# bac-bmb-t.net
KiCad netlist of a schematic drawn in EAGLE
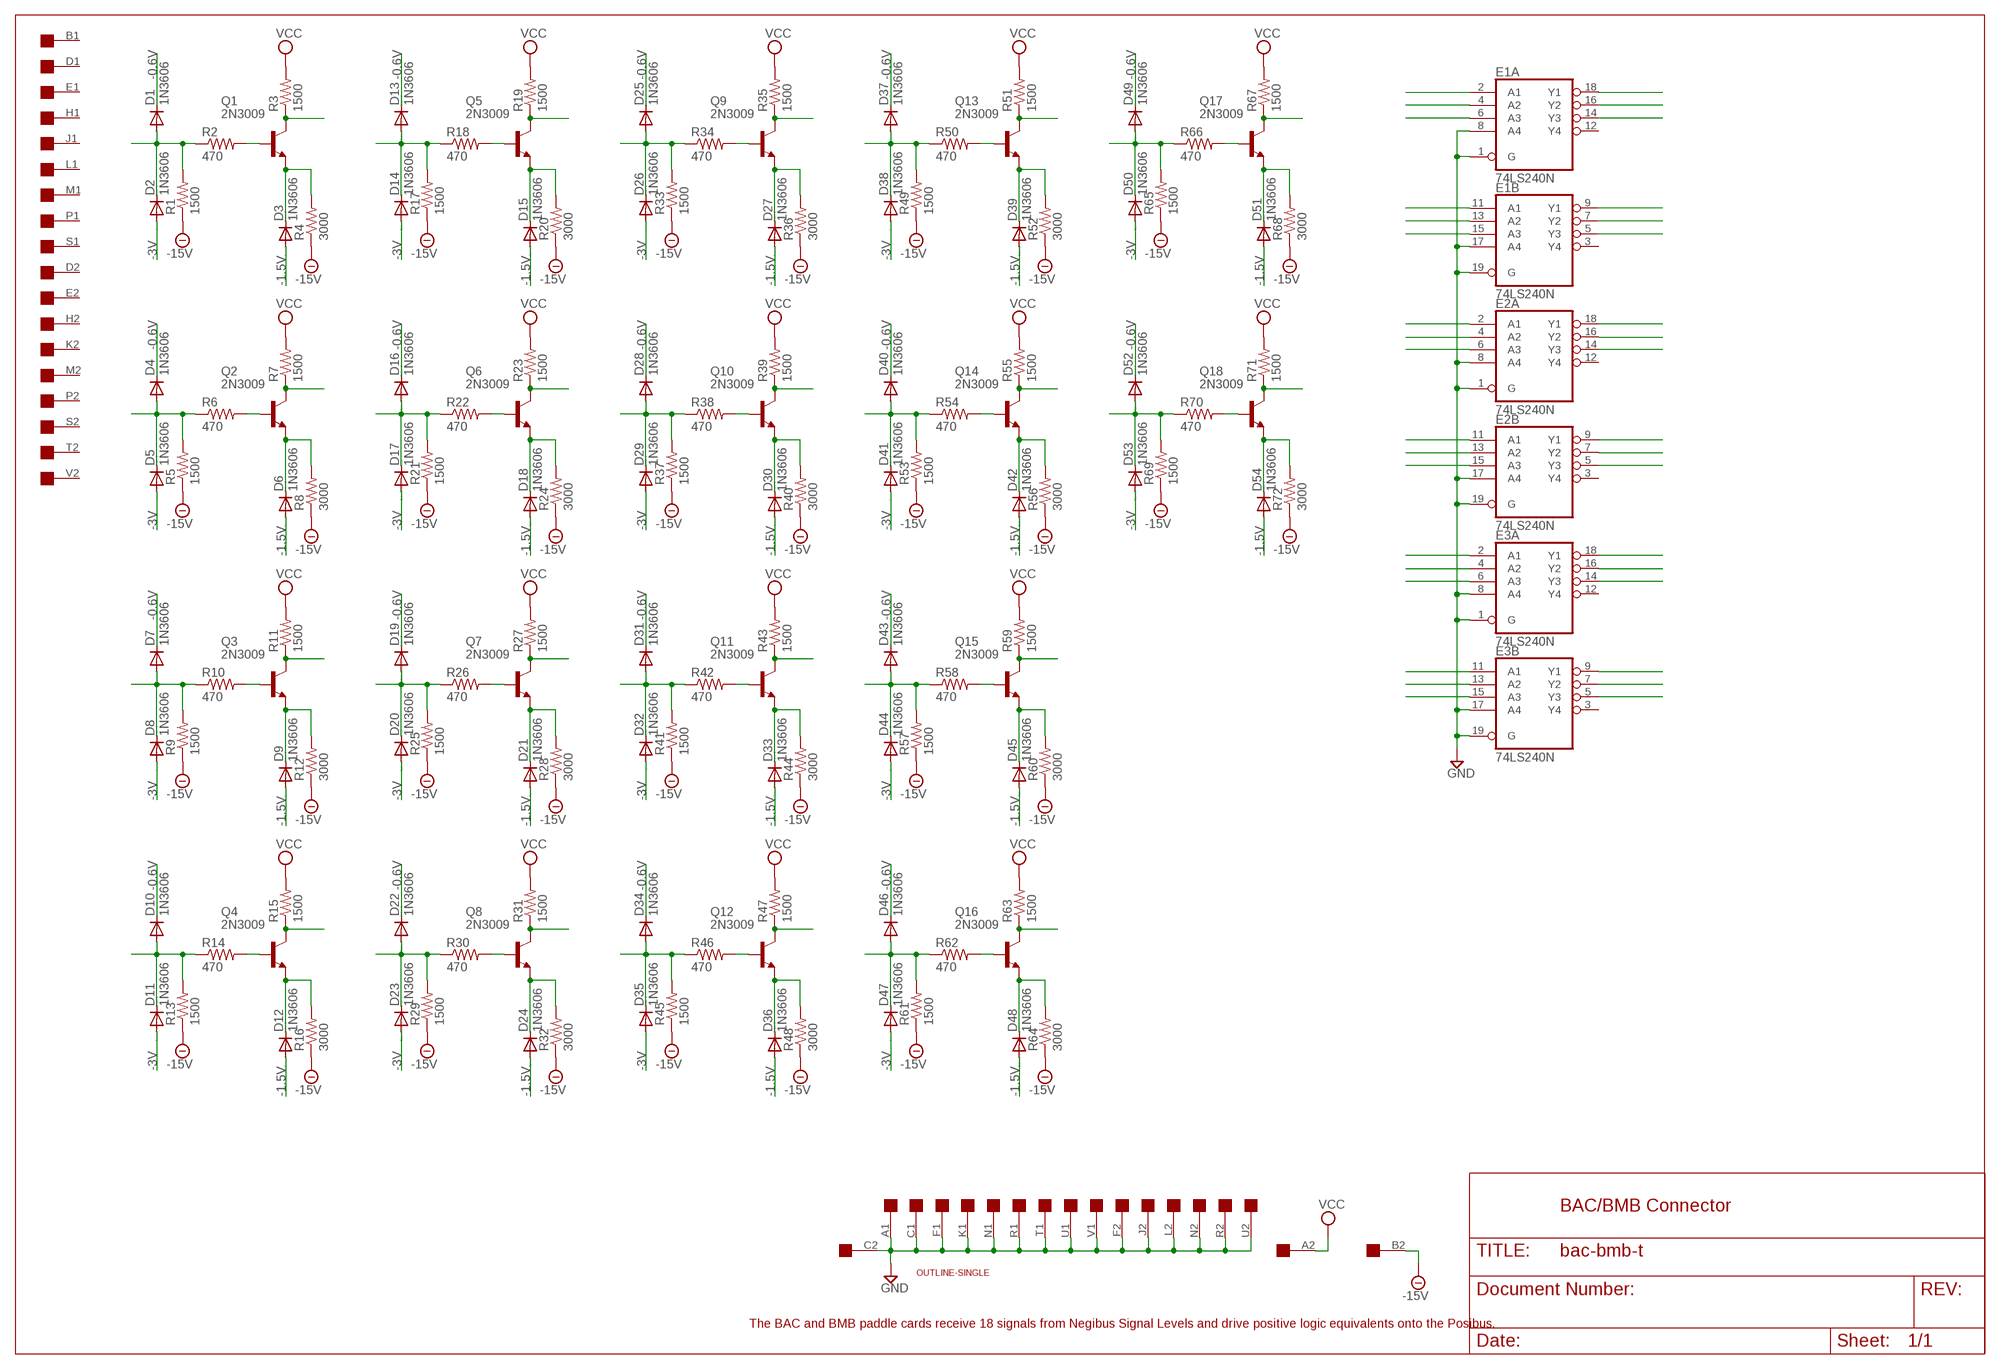
[diagram p0: schematic, sheet 1]

(export (version "E")
  (design (tool "Eeschema 10.0.6"))
  (components
    (comp (ref "D1")
      (value "1N3606")
      (footprint "eagle-import:DO35-10")
      (libsource (lib "eagle-import") (part "DIODE-DO35-10"))
    )
    (comp (ref "D2")
      (value "1N3606")
      (footprint "eagle-import:DO35-10")
      (libsource (lib "eagle-import") (part "DIODE-DO35-10"))
    )
    (comp (ref "D3")
      (value "1N3606")
      (footprint "eagle-import:DO35-10")
      (libsource (lib "eagle-import") (part "DIODE-DO35-10"))
    )
    (comp (ref "D4")
      (value "1N3606")
      (footprint "eagle-import:DO35-10")
      (libsource (lib "eagle-import") (part "DIODE-DO35-10"))
    )
    (comp (ref "D5")
      (value "1N3606")
      (footprint "eagle-import:DO35-10")
      (libsource (lib "eagle-import") (part "DIODE-DO35-10"))
    )
    (comp (ref "D6")
      (value "1N3606")
      (footprint "eagle-import:DO35-10")
      (libsource (lib "eagle-import") (part "DIODE-DO35-10"))
    )
    (comp (ref "D7")
      (value "1N3606")
      (footprint "eagle-import:DO35-10")
      (libsource (lib "eagle-import") (part "DIODE-DO35-10"))
    )
    (comp (ref "D8")
      (value "1N3606")
      (footprint "eagle-import:DO35-10")
      (libsource (lib "eagle-import") (part "DIODE-DO35-10"))
    )
    (comp (ref "D9")
      (value "1N3606")
      (footprint "eagle-import:DO35-10")
      (libsource (lib "eagle-import") (part "DIODE-DO35-10"))
    )
    (comp (ref "D10")
      (value "1N3606")
      (footprint "eagle-import:DO35-10")
      (libsource (lib "eagle-import") (part "DIODE-DO35-10"))
    )
    (comp (ref "D11")
      (value "1N3606")
      (footprint "eagle-import:DO35-10")
      (libsource (lib "eagle-import") (part "DIODE-DO35-10"))
    )
    (comp (ref "D12")
      (value "1N3606")
      (footprint "eagle-import:DO35-10")
      (libsource (lib "eagle-import") (part "DIODE-DO35-10"))
    )
    (comp (ref "D13")
      (value "1N3606")
      (footprint "eagle-import:DO35-10")
      (libsource (lib "eagle-import") (part "DIODE-DO35-10"))
    )
    (comp (ref "D14")
      (value "1N3606")
      (footprint "eagle-import:DO35-10")
      (libsource (lib "eagle-import") (part "DIODE-DO35-10"))
    )
    (comp (ref "D15")
      (value "1N3606")
      (footprint "eagle-import:DO35-10")
      (libsource (lib "eagle-import") (part "DIODE-DO35-10"))
    )
    (comp (ref "D16")
      (value "1N3606")
      (footprint "eagle-import:DO35-10")
      (libsource (lib "eagle-import") (part "DIODE-DO35-10"))
    )
    (comp (ref "D17")
      (value "1N3606")
      (footprint "eagle-import:DO35-10")
      (libsource (lib "eagle-import") (part "DIODE-DO35-10"))
    )
    (comp (ref "D18")
      (value "1N3606")
      (footprint "eagle-import:DO35-10")
      (libsource (lib "eagle-import") (part "DIODE-DO35-10"))
    )
    (comp (ref "D19")
      (value "1N3606")
      (footprint "eagle-import:DO35-10")
      (libsource (lib "eagle-import") (part "DIODE-DO35-10"))
    )
    (comp (ref "D20")
      (value "1N3606")
      (footprint "eagle-import:DO35-10")
      (libsource (lib "eagle-import") (part "DIODE-DO35-10"))
    )
    (comp (ref "D21")
      (value "1N3606")
      (footprint "eagle-import:DO35-10")
      (libsource (lib "eagle-import") (part "DIODE-DO35-10"))
    )
    (comp (ref "D22")
      (value "1N3606")
      (footprint "eagle-import:DO35-10")
      (libsource (lib "eagle-import") (part "DIODE-DO35-10"))
    )
    (comp (ref "D23")
      (value "1N3606")
      (footprint "eagle-import:DO35-10")
      (libsource (lib "eagle-import") (part "DIODE-DO35-10"))
    )
    (comp (ref "D24")
      (value "1N3606")
      (footprint "eagle-import:DO35-10")
      (libsource (lib "eagle-import") (part "DIODE-DO35-10"))
    )
    (comp (ref "D25")
      (value "1N3606")
      (footprint "eagle-import:DO35-10")
      (libsource (lib "eagle-import") (part "DIODE-DO35-10"))
    )
    (comp (ref "D26")
      (value "1N3606")
      (footprint "eagle-import:DO35-10")
      (libsource (lib "eagle-import") (part "DIODE-DO35-10"))
    )
    (comp (ref "D27")
      (value "1N3606")
      (footprint "eagle-import:DO35-10")
      (libsource (lib "eagle-import") (part "DIODE-DO35-10"))
    )
    (comp (ref "D28")
      (value "1N3606")
      (footprint "eagle-import:DO35-10")
      (libsource (lib "eagle-import") (part "DIODE-DO35-10"))
    )
    (comp (ref "D29")
      (value "1N3606")
      (footprint "eagle-import:DO35-10")
      (libsource (lib "eagle-import") (part "DIODE-DO35-10"))
    )
    (comp (ref "D30")
      (value "1N3606")
      (footprint "eagle-import:DO35-10")
      (libsource (lib "eagle-import") (part "DIODE-DO35-10"))
    )
    (comp (ref "D31")
      (value "1N3606")
      (footprint "eagle-import:DO35-10")
      (libsource (lib "eagle-import") (part "DIODE-DO35-10"))
    )
    (comp (ref "D32")
      (value "1N3606")
      (footprint "eagle-import:DO35-10")
      (libsource (lib "eagle-import") (part "DIODE-DO35-10"))
    )
    (comp (ref "D33")
      (value "1N3606")
      (footprint "eagle-import:DO35-10")
      (libsource (lib "eagle-import") (part "DIODE-DO35-10"))
    )
    (comp (ref "D34")
      (value "1N3606")
      (footprint "eagle-import:DO35-10")
      (libsource (lib "eagle-import") (part "DIODE-DO35-10"))
    )
    (comp (ref "D35")
      (value "1N3606")
      (footprint "eagle-import:DO35-10")
      (libsource (lib "eagle-import") (part "DIODE-DO35-10"))
    )
    (comp (ref "D36")
      (value "1N3606")
      (footprint "eagle-import:DO35-10")
      (libsource (lib "eagle-import") (part "DIODE-DO35-10"))
    )
    (comp (ref "D37")
      (value "1N3606")
      (footprint "eagle-import:DO35-10")
      (libsource (lib "eagle-import") (part "DIODE-DO35-10"))
    )
    (comp (ref "D38")
      (value "1N3606")
      (footprint "eagle-import:DO35-10")
      (libsource (lib "eagle-import") (part "DIODE-DO35-10"))
    )
    (comp (ref "D39")
      (value "1N3606")
      (footprint "eagle-import:DO35-10")
      (libsource (lib "eagle-import") (part "DIODE-DO35-10"))
    )
    (comp (ref "D40")
      (value "1N3606")
      (footprint "eagle-import:DO35-10")
      (libsource (lib "eagle-import") (part "DIODE-DO35-10"))
    )
    (comp (ref "D41")
      (value "1N3606")
      (footprint "eagle-import:DO35-10")
      (libsource (lib "eagle-import") (part "DIODE-DO35-10"))
    )
    (comp (ref "D42")
      (value "1N3606")
      (footprint "eagle-import:DO35-10")
      (libsource (lib "eagle-import") (part "DIODE-DO35-10"))
    )
    (comp (ref "D43")
      (value "1N3606")
      (footprint "eagle-import:DO35-10")
      (libsource (lib "eagle-import") (part "DIODE-DO35-10"))
    )
    (comp (ref "D44")
      (value "1N3606")
      (footprint "eagle-import:DO35-10")
      (libsource (lib "eagle-import") (part "DIODE-DO35-10"))
    )
    (comp (ref "D45")
      (value "1N3606")
      (footprint "eagle-import:DO35-10")
      (libsource (lib "eagle-import") (part "DIODE-DO35-10"))
    )
    (comp (ref "D46")
      (value "1N3606")
      (footprint "eagle-import:DO35-10")
      (libsource (lib "eagle-import") (part "DIODE-DO35-10"))
    )
    (comp (ref "D47")
      (value "1N3606")
      (footprint "eagle-import:DO35-10")
      (libsource (lib "eagle-import") (part "DIODE-DO35-10"))
    )
    (comp (ref "D48")
      (value "1N3606")
      (footprint "eagle-import:DO35-10")
      (libsource (lib "eagle-import") (part "DIODE-DO35-10"))
    )
    (comp (ref "D49")
      (value "1N3606")
      (footprint "eagle-import:DO35-10")
      (libsource (lib "eagle-import") (part "DIODE-DO35-10"))
    )
    (comp (ref "D50")
      (value "1N3606")
      (footprint "eagle-import:DO35-10")
      (libsource (lib "eagle-import") (part "DIODE-DO35-10"))
    )
    (comp (ref "D51")
      (value "1N3606")
      (footprint "eagle-import:DO35-10")
      (libsource (lib "eagle-import") (part "DIODE-DO35-10"))
    )
    (comp (ref "D52")
      (value "1N3606")
      (footprint "eagle-import:DO35-10")
      (libsource (lib "eagle-import") (part "DIODE-DO35-10"))
    )
    (comp (ref "D53")
      (value "1N3606")
      (footprint "eagle-import:DO35-10")
      (libsource (lib "eagle-import") (part "DIODE-DO35-10"))
    )
    (comp (ref "D54")
      (value "1N3606")
      (footprint "eagle-import:DO35-10")
      (libsource (lib "eagle-import") (part "DIODE-DO35-10"))
    )
    (comp (ref "E1")
      (value "74LS240N")
      (footprint "eagle-import:DIL20")
      (libsource (lib "eagle-import") (part "74240NLS"))
    )
    (comp (ref "E2")
      (value "74LS240N")
      (footprint "eagle-import:DIL20")
      (libsource (lib "eagle-import") (part "74240NLS"))
    )
    (comp (ref "E3")
      (value "74LS240N")
      (footprint "eagle-import:DIL20")
      (libsource (lib "eagle-import") (part "74240NLS"))
    )
    (comp (ref "Q1")
      (value "2N3009")
      (footprint "eagle-import:TO5")
      (libsource (lib "eagle-import") (part "-NPN-TO5"))
    )
    (comp (ref "Q2")
      (value "2N3009")
      (footprint "eagle-import:TO5")
      (libsource (lib "eagle-import") (part "-NPN-TO5"))
    )
    (comp (ref "Q3")
      (value "2N3009")
      (footprint "eagle-import:TO5")
      (libsource (lib "eagle-import") (part "-NPN-TO5"))
    )
    (comp (ref "Q4")
      (value "2N3009")
      (footprint "eagle-import:TO5")
      (libsource (lib "eagle-import") (part "-NPN-TO5"))
    )
    (comp (ref "Q5")
      (value "2N3009")
      (footprint "eagle-import:TO5")
      (libsource (lib "eagle-import") (part "-NPN-TO5"))
    )
    (comp (ref "Q6")
      (value "2N3009")
      (footprint "eagle-import:TO5")
      (libsource (lib "eagle-import") (part "-NPN-TO5"))
    )
    (comp (ref "Q7")
      (value "2N3009")
      (footprint "eagle-import:TO5")
      (libsource (lib "eagle-import") (part "-NPN-TO5"))
    )
    (comp (ref "Q8")
      (value "2N3009")
      (footprint "eagle-import:TO5")
      (libsource (lib "eagle-import") (part "-NPN-TO5"))
    )
    (comp (ref "Q9")
      (value "2N3009")
      (footprint "eagle-import:TO5")
      (libsource (lib "eagle-import") (part "-NPN-TO5"))
    )
    (comp (ref "Q10")
      (value "2N3009")
      (footprint "eagle-import:TO5")
      (libsource (lib "eagle-import") (part "-NPN-TO5"))
    )
    (comp (ref "Q11")
      (value "2N3009")
      (footprint "eagle-import:TO5")
      (libsource (lib "eagle-import") (part "-NPN-TO5"))
    )
    (comp (ref "Q12")
      (value "2N3009")
      (footprint "eagle-import:TO5")
      (libsource (lib "eagle-import") (part "-NPN-TO5"))
    )
    (comp (ref "Q13")
      (value "2N3009")
      (footprint "eagle-import:TO5")
      (libsource (lib "eagle-import") (part "-NPN-TO5"))
    )
    (comp (ref "Q14")
      (value "2N3009")
      (footprint "eagle-import:TO5")
      (libsource (lib "eagle-import") (part "-NPN-TO5"))
    )
    (comp (ref "Q15")
      (value "2N3009")
      (footprint "eagle-import:TO5")
      (libsource (lib "eagle-import") (part "-NPN-TO5"))
    )
    (comp (ref "Q16")
      (value "2N3009")
      (footprint "eagle-import:TO5")
      (libsource (lib "eagle-import") (part "-NPN-TO5"))
    )
    (comp (ref "Q17")
      (value "2N3009")
      (footprint "eagle-import:TO5")
      (libsource (lib "eagle-import") (part "-NPN-TO5"))
    )
    (comp (ref "Q18")
      (value "2N3009")
      (footprint "eagle-import:TO5")
      (libsource (lib "eagle-import") (part "-NPN-TO5"))
    )
    (comp (ref "R1")
      (value "1500")
      (footprint "eagle-import:0207_10")
      (libsource (lib "eagle-import") (part "R-US_0207/10"))
    )
    (comp (ref "R2")
      (value "470")
      (footprint "eagle-import:0207_10")
      (libsource (lib "eagle-import") (part "R-US_0207/10"))
    )
    (comp (ref "R3")
      (value "1500")
      (footprint "eagle-import:0207_10")
      (libsource (lib "eagle-import") (part "R-US_0207/10"))
    )
    (comp (ref "R4")
      (value "3000")
      (footprint "eagle-import:0207_10")
      (libsource (lib "eagle-import") (part "R-US_0207/10"))
    )
    (comp (ref "R5")
      (value "1500")
      (footprint "eagle-import:0207_10")
      (libsource (lib "eagle-import") (part "R-US_0207/10"))
    )
    (comp (ref "R6")
      (value "470")
      (footprint "eagle-import:0207_10")
      (libsource (lib "eagle-import") (part "R-US_0207/10"))
    )
    (comp (ref "R7")
      (value "1500")
      (footprint "eagle-import:0207_10")
      (libsource (lib "eagle-import") (part "R-US_0207/10"))
    )
    (comp (ref "R8")
      (value "3000")
      (footprint "eagle-import:0207_10")
      (libsource (lib "eagle-import") (part "R-US_0207/10"))
    )
    (comp (ref "R9")
      (value "1500")
      (footprint "eagle-import:0207_10")
      (libsource (lib "eagle-import") (part "R-US_0207/10"))
    )
    (comp (ref "R10")
      (value "470")
      (footprint "eagle-import:0207_10")
      (libsource (lib "eagle-import") (part "R-US_0207/10"))
    )
    (comp (ref "R11")
      (value "1500")
      (footprint "eagle-import:0207_10")
      (libsource (lib "eagle-import") (part "R-US_0207/10"))
    )
    (comp (ref "R12")
      (value "3000")
      (footprint "eagle-import:0207_10")
      (libsource (lib "eagle-import") (part "R-US_0207/10"))
    )
    (comp (ref "R13")
      (value "1500")
      (footprint "eagle-import:0207_10")
      (libsource (lib "eagle-import") (part "R-US_0207/10"))
    )
    (comp (ref "R14")
      (value "470")
      (footprint "eagle-import:0207_10")
      (libsource (lib "eagle-import") (part "R-US_0207/10"))
    )
    (comp (ref "R15")
      (value "1500")
      (footprint "eagle-import:0207_10")
      (libsource (lib "eagle-import") (part "R-US_0207/10"))
    )
    (comp (ref "R16")
      (value "3000")
      (footprint "eagle-import:0207_10")
      (libsource (lib "eagle-import") (part "R-US_0207/10"))
    )
    (comp (ref "R17")
      (value "1500")
      (footprint "eagle-import:0207_10")
      (libsource (lib "eagle-import") (part "R-US_0207/10"))
    )
    (comp (ref "R18")
      (value "470")
      (footprint "eagle-import:0207_10")
      (libsource (lib "eagle-import") (part "R-US_0207/10"))
    )
    (comp (ref "R19")
      (value "1500")
      (footprint "eagle-import:0207_10")
      (libsource (lib "eagle-import") (part "R-US_0207/10"))
    )
    (comp (ref "R20")
      (value "3000")
      (footprint "eagle-import:0207_10")
      (libsource (lib "eagle-import") (part "R-US_0207/10"))
    )
    (comp (ref "R21")
      (value "1500")
      (footprint "eagle-import:0207_10")
      (libsource (lib "eagle-import") (part "R-US_0207/10"))
    )
    (comp (ref "R22")
      (value "470")
      (footprint "eagle-import:0207_10")
      (libsource (lib "eagle-import") (part "R-US_0207/10"))
    )
    (comp (ref "R23")
      (value "1500")
      (footprint "eagle-import:0207_10")
      (libsource (lib "eagle-import") (part "R-US_0207/10"))
    )
    (comp (ref "R24")
      (value "3000")
      (footprint "eagle-import:0207_10")
      (libsource (lib "eagle-import") (part "R-US_0207/10"))
    )
    (comp (ref "R25")
      (value "1500")
      (footprint "eagle-import:0207_10")
      (libsource (lib "eagle-import") (part "R-US_0207/10"))
    )
    (comp (ref "R26")
      (value "470")
      (footprint "eagle-import:0207_10")
      (libsource (lib "eagle-import") (part "R-US_0207/10"))
    )
    (comp (ref "R27")
      (value "1500")
      (footprint "eagle-import:0207_10")
      (libsource (lib "eagle-import") (part "R-US_0207/10"))
    )
    (comp (ref "R28")
      (value "3000")
      (footprint "eagle-import:0207_10")
      (libsource (lib "eagle-import") (part "R-US_0207/10"))
    )
    (comp (ref "R29")
      (value "1500")
      (footprint "eagle-import:0207_10")
      (libsource (lib "eagle-import") (part "R-US_0207/10"))
    )
    (comp (ref "R30")
      (value "470")
      (footprint "eagle-import:0207_10")
      (libsource (lib "eagle-import") (part "R-US_0207/10"))
    )
    (comp (ref "R31")
      (value "1500")
      (footprint "eagle-import:0207_10")
      (libsource (lib "eagle-import") (part "R-US_0207/10"))
    )
    (comp (ref "R32")
      (value "3000")
      (footprint "eagle-import:0207_10")
      (libsource (lib "eagle-import") (part "R-US_0207/10"))
    )
    (comp (ref "R33")
      (value "1500")
      (footprint "eagle-import:0207_10")
      (libsource (lib "eagle-import") (part "R-US_0207/10"))
    )
    (comp (ref "R34")
      (value "470")
      (footprint "eagle-import:0207_10")
      (libsource (lib "eagle-import") (part "R-US_0207/10"))
    )
    (comp (ref "R35")
      (value "1500")
      (footprint "eagle-import:0207_10")
      (libsource (lib "eagle-import") (part "R-US_0207/10"))
    )
    (comp (ref "R36")
      (value "3000")
      (footprint "eagle-import:0207_10")
      (libsource (lib "eagle-import") (part "R-US_0207/10"))
    )
    (comp (ref "R37")
      (value "1500")
      (footprint "eagle-import:0207_10")
      (libsource (lib "eagle-import") (part "R-US_0207/10"))
    )
    (comp (ref "R38")
      (value "470")
      (footprint "eagle-import:0207_10")
      (libsource (lib "eagle-import") (part "R-US_0207/10"))
    )
    (comp (ref "R39")
      (value "1500")
      (footprint "eagle-import:0207_10")
      (libsource (lib "eagle-import") (part "R-US_0207/10"))
    )
    (comp (ref "R40")
      (value "3000")
      (footprint "eagle-import:0207_10")
      (libsource (lib "eagle-import") (part "R-US_0207/10"))
    )
    (comp (ref "R41")
      (value "1500")
      (footprint "eagle-import:0207_10")
      (libsource (lib "eagle-import") (part "R-US_0207/10"))
    )
    (comp (ref "R42")
      (value "470")
      (footprint "eagle-import:0207_10")
      (libsource (lib "eagle-import") (part "R-US_0207/10"))
    )
    (comp (ref "R43")
      (value "1500")
      (footprint "eagle-import:0207_10")
      (libsource (lib "eagle-import") (part "R-US_0207/10"))
    )
    (comp (ref "R44")
      (value "3000")
      (footprint "eagle-import:0207_10")
      (libsource (lib "eagle-import") (part "R-US_0207/10"))
    )
    (comp (ref "R45")
      (value "1500")
      (footprint "eagle-import:0207_10")
      (libsource (lib "eagle-import") (part "R-US_0207/10"))
    )
    (comp (ref "R46")
      (value "470")
      (footprint "eagle-import:0207_10")
      (libsource (lib "eagle-import") (part "R-US_0207/10"))
    )
    (comp (ref "R47")
      (value "1500")
      (footprint "eagle-import:0207_10")
      (libsource (lib "eagle-import") (part "R-US_0207/10"))
    )
    (comp (ref "R48")
      (value "3000")
      (footprint "eagle-import:0207_10")
      (libsource (lib "eagle-import") (part "R-US_0207/10"))
    )
    (comp (ref "R49")
      (value "1500")
      (footprint "eagle-import:0207_10")
      (libsource (lib "eagle-import") (part "R-US_0207/10"))
    )
    (comp (ref "R50")
      (value "470")
      (footprint "eagle-import:0207_10")
      (libsource (lib "eagle-import") (part "R-US_0207/10"))
    )
    (comp (ref "R51")
      (value "1500")
      (footprint "eagle-import:0207_10")
      (libsource (lib "eagle-import") (part "R-US_0207/10"))
    )
    (comp (ref "R52")
      (value "3000")
      (footprint "eagle-import:0207_10")
      (libsource (lib "eagle-import") (part "R-US_0207/10"))
    )
    (comp (ref "R53")
      (value "1500")
      (footprint "eagle-import:0207_10")
      (libsource (lib "eagle-import") (part "R-US_0207/10"))
    )
    (comp (ref "R54")
      (value "470")
      (footprint "eagle-import:0207_10")
      (libsource (lib "eagle-import") (part "R-US_0207/10"))
    )
    (comp (ref "R55")
      (value "1500")
      (footprint "eagle-import:0207_10")
      (libsource (lib "eagle-import") (part "R-US_0207/10"))
    )
    (comp (ref "R56")
      (value "3000")
      (footprint "eagle-import:0207_10")
      (libsource (lib "eagle-import") (part "R-US_0207/10"))
    )
    (comp (ref "R57")
      (value "1500")
      (footprint "eagle-import:0207_10")
      (libsource (lib "eagle-import") (part "R-US_0207/10"))
    )
    (comp (ref "R58")
      (value "470")
      (footprint "eagle-import:0207_10")
      (libsource (lib "eagle-import") (part "R-US_0207/10"))
    )
    (comp (ref "R59")
      (value "1500")
      (footprint "eagle-import:0207_10")
      (libsource (lib "eagle-import") (part "R-US_0207/10"))
    )
    (comp (ref "R60")
      (value "3000")
      (footprint "eagle-import:0207_10")
      (libsource (lib "eagle-import") (part "R-US_0207/10"))
    )
    (comp (ref "R61")
      (value "1500")
      (footprint "eagle-import:0207_10")
      (libsource (lib "eagle-import") (part "R-US_0207/10"))
    )
    (comp (ref "R62")
      (value "470")
      (footprint "eagle-import:0207_10")
      (libsource (lib "eagle-import") (part "R-US_0207/10"))
    )
    (comp (ref "R63")
      (value "1500")
      (footprint "eagle-import:0207_10")
      (libsource (lib "eagle-import") (part "R-US_0207/10"))
    )
    (comp (ref "R64")
      (value "3000")
      (footprint "eagle-import:0207_10")
      (libsource (lib "eagle-import") (part "R-US_0207/10"))
    )
    (comp (ref "R65")
      (value "1500")
      (footprint "eagle-import:0207_10")
      (libsource (lib "eagle-import") (part "R-US_0207/10"))
    )
    (comp (ref "R66")
      (value "470")
      (footprint "eagle-import:0207_10")
      (libsource (lib "eagle-import") (part "R-US_0207/10"))
    )
    (comp (ref "R67")
      (value "1500")
      (footprint "eagle-import:0207_10")
      (libsource (lib "eagle-import") (part "R-US_0207/10"))
    )
    (comp (ref "R68")
      (value "3000")
      (footprint "eagle-import:0207_10")
      (libsource (lib "eagle-import") (part "R-US_0207/10"))
    )
    (comp (ref "R69")
      (value "1500")
      (footprint "eagle-import:0207_10")
      (libsource (lib "eagle-import") (part "R-US_0207/10"))
    )
    (comp (ref "R70")
      (value "470")
      (footprint "eagle-import:0207_10")
      (libsource (lib "eagle-import") (part "R-US_0207/10"))
    )
    (comp (ref "R71")
      (value "1500")
      (footprint "eagle-import:0207_10")
      (libsource (lib "eagle-import") (part "R-US_0207/10"))
    )
    (comp (ref "R72")
      (value "3000")
      (footprint "eagle-import:0207_10")
      (libsource (lib "eagle-import") (part "R-US_0207/10"))
    )
    (comp (ref "U$1")
      (value "SINGLE")
      (footprint "eagle-import:EDGE-CON2")
      (libsource (lib "eagle-import") (part "SINGLE"))
    )
    (comp (ref "U$2")
      (value "OUTLINE-SINGLE")
      (footprint "eagle-import:SINGLE")
      (libsource (lib "eagle-import") (part "OUTLINE-SINGLE"))
    )
  )
  (nets
    (net (code "1") (name "-15V") (class "Default")
      (node (ref "R1") (pin "1") (pinfunction "1_1") (pintype "passive"))
      (node (ref "R12") (pin "1") (pinfunction "1_1") (pintype "passive"))
      (node (ref "R13") (pin "1") (pinfunction "1_1") (pintype "passive"))
      (node (ref "R16") (pin "1") (pinfunction "1_1") (pintype "passive"))
      (node (ref "R17") (pin "1") (pinfunction "1_1") (pintype "passive"))
      (node (ref "R20") (pin "1") (pinfunction "1_1") (pintype "passive"))
      (node (ref "R21") (pin "1") (pinfunction "1_1") (pintype "passive"))
      (node (ref "R24") (pin "1") (pinfunction "1_1") (pintype "passive"))
      (node (ref "R25") (pin "1") (pinfunction "1_1") (pintype "passive"))
      (node (ref "R28") (pin "1") (pinfunction "1_1") (pintype "passive"))
      (node (ref "R29") (pin "1") (pinfunction "1_1") (pintype "passive"))
      (node (ref "R32") (pin "1") (pinfunction "1_1") (pintype "passive"))
      (node (ref "R33") (pin "1") (pinfunction "1_1") (pintype "passive"))
      (node (ref "R36") (pin "1") (pinfunction "1_1") (pintype "passive"))
      (node (ref "R37") (pin "1") (pinfunction "1_1") (pintype "passive"))
      (node (ref "R4") (pin "1") (pinfunction "1_1") (pintype "passive"))
      (node (ref "R40") (pin "1") (pinfunction "1_1") (pintype "passive"))
      (node (ref "R41") (pin "1") (pinfunction "1_1") (pintype "passive"))
      (node (ref "R44") (pin "1") (pinfunction "1_1") (pintype "passive"))
      (node (ref "R45") (pin "1") (pinfunction "1_1") (pintype "passive"))
      (node (ref "R48") (pin "1") (pinfunction "1_1") (pintype "passive"))
      (node (ref "R49") (pin "1") (pinfunction "1_1") (pintype "passive"))
      (node (ref "R5") (pin "1") (pinfunction "1_1") (pintype "passive"))
      (node (ref "R52") (pin "1") (pinfunction "1_1") (pintype "passive"))
      (node (ref "R53") (pin "1") (pinfunction "1_1") (pintype "passive"))
      (node (ref "R56") (pin "1") (pinfunction "1_1") (pintype "passive"))
      (node (ref "R57") (pin "1") (pinfunction "1_1") (pintype "passive"))
      (node (ref "R60") (pin "1") (pinfunction "1_1") (pintype "passive"))
      (node (ref "R61") (pin "1") (pinfunction "1_1") (pintype "passive"))
      (node (ref "R64") (pin "1") (pinfunction "1_1") (pintype "passive"))
      (node (ref "R65") (pin "1") (pinfunction "1_1") (pintype "passive"))
      (node (ref "R68") (pin "1") (pinfunction "1_1") (pintype "passive"))
      (node (ref "R69") (pin "1") (pinfunction "1_1") (pintype "passive"))
      (node (ref "R72") (pin "1") (pinfunction "1_1") (pintype "passive"))
      (node (ref "R8") (pin "1") (pinfunction "1_1") (pintype "passive"))
      (node (ref "R9") (pin "1") (pinfunction "1_1") (pintype "passive"))
      (node (ref "U$1") (pin "B2") (pinfunction "1_B2") (pintype "bidirectional"))
    )
    (net (code "2") (name "/-0.6V") (class "Default")
      (node (ref "D1") (pin "C") (pinfunction "C_C") (pintype "passive"))
      (node (ref "D10") (pin "C") (pinfunction "C_C") (pintype "passive"))
      (node (ref "D13") (pin "C") (pinfunction "C_C") (pintype "passive"))
      (node (ref "D16") (pin "C") (pinfunction "C_C") (pintype "passive"))
      (node (ref "D19") (pin "C") (pinfunction "C_C") (pintype "passive"))
      (node (ref "D22") (pin "C") (pinfunction "C_C") (pintype "passive"))
      (node (ref "D25") (pin "C") (pinfunction "C_C") (pintype "passive"))
      (node (ref "D28") (pin "C") (pinfunction "C_C") (pintype "passive"))
      (node (ref "D31") (pin "C") (pinfunction "C_C") (pintype "passive"))
      (node (ref "D34") (pin "C") (pinfunction "C_C") (pintype "passive"))
      (node (ref "D37") (pin "C") (pinfunction "C_C") (pintype "passive"))
      (node (ref "D4") (pin "C") (pinfunction "C_C") (pintype "passive"))
      (node (ref "D40") (pin "C") (pinfunction "C_C") (pintype "passive"))
      (node (ref "D43") (pin "C") (pinfunction "C_C") (pintype "passive"))
      (node (ref "D46") (pin "C") (pinfunction "C_C") (pintype "passive"))
      (node (ref "D49") (pin "C") (pinfunction "C_C") (pintype "passive"))
      (node (ref "D52") (pin "C") (pinfunction "C_C") (pintype "passive"))
      (node (ref "D7") (pin "C") (pinfunction "C_C") (pintype "passive"))
    )
    (net (code "3") (name "/-1.5V") (class "Default")
      (node (ref "D12") (pin "A") (pinfunction "A_A") (pintype "passive"))
      (node (ref "D15") (pin "A") (pinfunction "A_A") (pintype "passive"))
      (node (ref "D18") (pin "A") (pinfunction "A_A") (pintype "passive"))
      (node (ref "D21") (pin "A") (pinfunction "A_A") (pintype "passive"))
      (node (ref "D24") (pin "A") (pinfunction "A_A") (pintype "passive"))
      (node (ref "D27") (pin "A") (pinfunction "A_A") (pintype "passive"))
      (node (ref "D3") (pin "A") (pinfunction "A_A") (pintype "passive"))
      (node (ref "D30") (pin "A") (pinfunction "A_A") (pintype "passive"))
      (node (ref "D33") (pin "A") (pinfunction "A_A") (pintype "passive"))
      (node (ref "D36") (pin "A") (pinfunction "A_A") (pintype "passive"))
      (node (ref "D39") (pin "A") (pinfunction "A_A") (pintype "passive"))
      (node (ref "D42") (pin "A") (pinfunction "A_A") (pintype "passive"))
      (node (ref "D45") (pin "A") (pinfunction "A_A") (pintype "passive"))
      (node (ref "D48") (pin "A") (pinfunction "A_A") (pintype "passive"))
      (node (ref "D51") (pin "A") (pinfunction "A_A") (pintype "passive"))
      (node (ref "D54") (pin "A") (pinfunction "A_A") (pintype "passive"))
      (node (ref "D6") (pin "A") (pinfunction "A_A") (pintype "passive"))
      (node (ref "D9") (pin "A") (pinfunction "A_A") (pintype "passive"))
    )
    (net (code "4") (name "/-3V") (class "Default")
      (node (ref "D11") (pin "A") (pinfunction "A_A") (pintype "passive"))
      (node (ref "D14") (pin "A") (pinfunction "A_A") (pintype "passive"))
      (node (ref "D17") (pin "A") (pinfunction "A_A") (pintype "passive"))
      (node (ref "D2") (pin "A") (pinfunction "A_A") (pintype "passive"))
      (node (ref "D20") (pin "A") (pinfunction "A_A") (pintype "passive"))
      (node (ref "D23") (pin "A") (pinfunction "A_A") (pintype "passive"))
      (node (ref "D26") (pin "A") (pinfunction "A_A") (pintype "passive"))
      (node (ref "D29") (pin "A") (pinfunction "A_A") (pintype "passive"))
      (node (ref "D32") (pin "A") (pinfunction "A_A") (pintype "passive"))
      (node (ref "D35") (pin "A") (pinfunction "A_A") (pintype "passive"))
      (node (ref "D38") (pin "A") (pinfunction "A_A") (pintype "passive"))
      (node (ref "D41") (pin "A") (pinfunction "A_A") (pintype "passive"))
      (node (ref "D44") (pin "A") (pinfunction "A_A") (pintype "passive"))
      (node (ref "D47") (pin "A") (pinfunction "A_A") (pintype "passive"))
      (node (ref "D5") (pin "A") (pinfunction "A_A") (pintype "passive"))
      (node (ref "D50") (pin "A") (pinfunction "A_A") (pintype "passive"))
      (node (ref "D53") (pin "A") (pinfunction "A_A") (pintype "passive"))
      (node (ref "D8") (pin "A") (pinfunction "A_A") (pintype "passive"))
    )
    (net (code "5") (name "GND") (class "Default")
      (node (ref "E1") (pin "1") (pinfunction "G_1") (pintype "input"))
      (node (ref "E1") (pin "17") (pinfunction "A4_17") (pintype "input"))
      (node (ref "E1") (pin "19") (pinfunction "G_19") (pintype "input"))
      (node (ref "E1") (pin "8") (pinfunction "A4_8") (pintype "input"))
      (node (ref "E2") (pin "1") (pinfunction "G_1") (pintype "input"))
      (node (ref "E2") (pin "17") (pinfunction "A4_17") (pintype "input"))
      (node (ref "E2") (pin "19") (pinfunction "G_19") (pintype "input"))
      (node (ref "E2") (pin "8") (pinfunction "A4_8") (pintype "input"))
      (node (ref "E3") (pin "1") (pinfunction "G_1") (pintype "input"))
      (node (ref "E3") (pin "17") (pinfunction "A4_17") (pintype "input"))
      (node (ref "E3") (pin "19") (pinfunction "G_19") (pintype "input"))
      (node (ref "E3") (pin "8") (pinfunction "A4_8") (pintype "input"))
      (node (ref "U$1") (pin "A1") (pinfunction "1_A1") (pintype "bidirectional"))
      (node (ref "U$1") (pin "C1") (pinfunction "1_C1") (pintype "bidirectional"))
      (node (ref "U$1") (pin "C2") (pinfunction "1_C2") (pintype "bidirectional"))
      (node (ref "U$1") (pin "F1") (pinfunction "1_F1") (pintype "bidirectional"))
      (node (ref "U$1") (pin "F2") (pinfunction "1_F2") (pintype "bidirectional"))
      (node (ref "U$1") (pin "J2") (pinfunction "1_J2") (pintype "bidirectional"))
      (node (ref "U$1") (pin "K1") (pinfunction "1_K1") (pintype "bidirectional"))
      (node (ref "U$1") (pin "L2") (pinfunction "1_L2") (pintype "bidirectional"))
      (node (ref "U$1") (pin "N1") (pinfunction "1_N1") (pintype "bidirectional"))
      (node (ref "U$1") (pin "N2") (pinfunction "1_N2") (pintype "bidirectional"))
      (node (ref "U$1") (pin "R1") (pinfunction "1_R1") (pintype "bidirectional"))
      (node (ref "U$1") (pin "R2") (pinfunction "1_R2") (pintype "bidirectional"))
      (node (ref "U$1") (pin "T1") (pinfunction "1_T1") (pintype "bidirectional"))
      (node (ref "U$1") (pin "U1") (pinfunction "1_U1") (pintype "bidirectional"))
      (node (ref "U$1") (pin "U2") (pinfunction "1_U2") (pintype "bidirectional"))
      (node (ref "U$1") (pin "V1") (pinfunction "1_V1") (pintype "bidirectional"))
    )
    (net (code "6") (name "Net-(D1-PadA)") (class "Default")
      (node (ref "D1") (pin "A") (pinfunction "A_A") (pintype "passive"))
      (node (ref "D2") (pin "C") (pinfunction "C_C") (pintype "passive"))
      (node (ref "R1") (pin "2") (pinfunction "2_2") (pintype "passive"))
      (node (ref "R2") (pin "1") (pinfunction "1_1") (pintype "passive"))
    )
    (net (code "7") (name "Net-(D4-PadA)") (class "Default")
      (node (ref "D4") (pin "A") (pinfunction "A_A") (pintype "passive"))
      (node (ref "D5") (pin "C") (pinfunction "C_C") (pintype "passive"))
      (node (ref "R5") (pin "2") (pinfunction "2_2") (pintype "passive"))
      (node (ref "R6") (pin "1") (pinfunction "1_1") (pintype "passive"))
    )
    (net (code "8") (name "Net-(D7-PadA)") (class "Default")
      (node (ref "D7") (pin "A") (pinfunction "A_A") (pintype "passive"))
      (node (ref "D8") (pin "C") (pinfunction "C_C") (pintype "passive"))
      (node (ref "R10") (pin "1") (pinfunction "1_1") (pintype "passive"))
      (node (ref "R9") (pin "2") (pinfunction "2_2") (pintype "passive"))
    )
    (net (code "9") (name "Net-(D10-PadA)") (class "Default")
      (node (ref "D10") (pin "A") (pinfunction "A_A") (pintype "passive"))
      (node (ref "D11") (pin "C") (pinfunction "C_C") (pintype "passive"))
      (node (ref "R13") (pin "2") (pinfunction "2_2") (pintype "passive"))
      (node (ref "R14") (pin "1") (pinfunction "1_1") (pintype "passive"))
    )
    (net (code "10") (name "Net-(D13-PadA)") (class "Default")
      (node (ref "D13") (pin "A") (pinfunction "A_A") (pintype "passive"))
      (node (ref "D14") (pin "C") (pinfunction "C_C") (pintype "passive"))
      (node (ref "R17") (pin "2") (pinfunction "2_2") (pintype "passive"))
      (node (ref "R18") (pin "1") (pinfunction "1_1") (pintype "passive"))
    )
    (net (code "11") (name "Net-(D16-PadA)") (class "Default")
      (node (ref "D16") (pin "A") (pinfunction "A_A") (pintype "passive"))
      (node (ref "D17") (pin "C") (pinfunction "C_C") (pintype "passive"))
      (node (ref "R21") (pin "2") (pinfunction "2_2") (pintype "passive"))
      (node (ref "R22") (pin "1") (pinfunction "1_1") (pintype "passive"))
    )
    (net (code "12") (name "Net-(D19-PadA)") (class "Default")
      (node (ref "D19") (pin "A") (pinfunction "A_A") (pintype "passive"))
      (node (ref "D20") (pin "C") (pinfunction "C_C") (pintype "passive"))
      (node (ref "R25") (pin "2") (pinfunction "2_2") (pintype "passive"))
      (node (ref "R26") (pin "1") (pinfunction "1_1") (pintype "passive"))
    )
    (net (code "13") (name "Net-(D22-PadA)") (class "Default")
      (node (ref "D22") (pin "A") (pinfunction "A_A") (pintype "passive"))
      (node (ref "D23") (pin "C") (pinfunction "C_C") (pintype "passive"))
      (node (ref "R29") (pin "2") (pinfunction "2_2") (pintype "passive"))
      (node (ref "R30") (pin "1") (pinfunction "1_1") (pintype "passive"))
    )
    (net (code "14") (name "Net-(D25-PadA)") (class "Default")
      (node (ref "D25") (pin "A") (pinfunction "A_A") (pintype "passive"))
      (node (ref "D26") (pin "C") (pinfunction "C_C") (pintype "passive"))
      (node (ref "R33") (pin "2") (pinfunction "2_2") (pintype "passive"))
      (node (ref "R34") (pin "1") (pinfunction "1_1") (pintype "passive"))
    )
    (net (code "15") (name "Net-(D28-PadA)") (class "Default")
      (node (ref "D28") (pin "A") (pinfunction "A_A") (pintype "passive"))
      (node (ref "D29") (pin "C") (pinfunction "C_C") (pintype "passive"))
      (node (ref "R37") (pin "2") (pinfunction "2_2") (pintype "passive"))
      (node (ref "R38") (pin "1") (pinfunction "1_1") (pintype "passive"))
    )
    (net (code "16") (name "Net-(D31-PadA)") (class "Default")
      (node (ref "D31") (pin "A") (pinfunction "A_A") (pintype "passive"))
      (node (ref "D32") (pin "C") (pinfunction "C_C") (pintype "passive"))
      (node (ref "R41") (pin "2") (pinfunction "2_2") (pintype "passive"))
      (node (ref "R42") (pin "1") (pinfunction "1_1") (pintype "passive"))
    )
    (net (code "17") (name "Net-(D34-PadA)") (class "Default")
      (node (ref "D34") (pin "A") (pinfunction "A_A") (pintype "passive"))
      (node (ref "D35") (pin "C") (pinfunction "C_C") (pintype "passive"))
      (node (ref "R45") (pin "2") (pinfunction "2_2") (pintype "passive"))
      (node (ref "R46") (pin "1") (pinfunction "1_1") (pintype "passive"))
    )
    (net (code "18") (name "Net-(D37-PadA)") (class "Default")
      (node (ref "D37") (pin "A") (pinfunction "A_A") (pintype "passive"))
      (node (ref "D38") (pin "C") (pinfunction "C_C") (pintype "passive"))
      (node (ref "R49") (pin "2") (pinfunction "2_2") (pintype "passive"))
      (node (ref "R50") (pin "1") (pinfunction "1_1") (pintype "passive"))
    )
    (net (code "19") (name "Net-(D40-PadA)") (class "Default")
      (node (ref "D40") (pin "A") (pinfunction "A_A") (pintype "passive"))
      (node (ref "D41") (pin "C") (pinfunction "C_C") (pintype "passive"))
      (node (ref "R53") (pin "2") (pinfunction "2_2") (pintype "passive"))
      (node (ref "R54") (pin "1") (pinfunction "1_1") (pintype "passive"))
    )
    (net (code "20") (name "Net-(D43-PadA)") (class "Default")
      (node (ref "D43") (pin "A") (pinfunction "A_A") (pintype "passive"))
      (node (ref "D44") (pin "C") (pinfunction "C_C") (pintype "passive"))
      (node (ref "R57") (pin "2") (pinfunction "2_2") (pintype "passive"))
      (node (ref "R58") (pin "1") (pinfunction "1_1") (pintype "passive"))
    )
    (net (code "21") (name "Net-(D46-PadA)") (class "Default")
      (node (ref "D46") (pin "A") (pinfunction "A_A") (pintype "passive"))
      (node (ref "D47") (pin "C") (pinfunction "C_C") (pintype "passive"))
      (node (ref "R61") (pin "2") (pinfunction "2_2") (pintype "passive"))
      (node (ref "R62") (pin "1") (pinfunction "1_1") (pintype "passive"))
    )
    (net (code "22") (name "Net-(D49-PadA)") (class "Default")
      (node (ref "D49") (pin "A") (pinfunction "A_A") (pintype "passive"))
      (node (ref "D50") (pin "C") (pinfunction "C_C") (pintype "passive"))
      (node (ref "R65") (pin "2") (pinfunction "2_2") (pintype "passive"))
      (node (ref "R66") (pin "1") (pinfunction "1_1") (pintype "passive"))
    )
    (net (code "23") (name "Net-(D52-PadA)") (class "Default")
      (node (ref "D52") (pin "A") (pinfunction "A_A") (pintype "passive"))
      (node (ref "D53") (pin "C") (pinfunction "C_C") (pintype "passive"))
      (node (ref "R69") (pin "2") (pinfunction "2_2") (pintype "passive"))
      (node (ref "R70") (pin "1") (pinfunction "1_1") (pintype "passive"))
    )
    (net (code "24") (name "Net-(Q1-B)") (class "Default")
      (node (ref "Q1") (pin "2") (pinfunction "B_2") (pintype "passive"))
      (node (ref "R2") (pin "2") (pinfunction "2_2") (pintype "passive"))
    )
    (net (code "25") (name "Net-(Q1-C)") (class "Default")
      (node (ref "Q1") (pin "3") (pinfunction "C_3") (pintype "passive"))
      (node (ref "R3") (pin "1") (pinfunction "1_1") (pintype "passive"))
    )
    (net (code "26") (name "Net-(Q1-E)") (class "Default")
      (node (ref "D3") (pin "C") (pinfunction "C_C") (pintype "passive"))
      (node (ref "Q1") (pin "1") (pinfunction "E_1") (pintype "passive"))
      (node (ref "R4") (pin "2") (pinfunction "2_2") (pintype "passive"))
    )
    (net (code "27") (name "Net-(Q2-B)") (class "Default")
      (node (ref "Q2") (pin "2") (pinfunction "B_2") (pintype "passive"))
      (node (ref "R6") (pin "2") (pinfunction "2_2") (pintype "passive"))
    )
    (net (code "28") (name "Net-(Q2-C)") (class "Default")
      (node (ref "Q2") (pin "3") (pinfunction "C_3") (pintype "passive"))
      (node (ref "R7") (pin "1") (pinfunction "1_1") (pintype "passive"))
    )
    (net (code "29") (name "Net-(Q2-E)") (class "Default")
      (node (ref "D6") (pin "C") (pinfunction "C_C") (pintype "passive"))
      (node (ref "Q2") (pin "1") (pinfunction "E_1") (pintype "passive"))
      (node (ref "R8") (pin "2") (pinfunction "2_2") (pintype "passive"))
    )
    (net (code "30") (name "Net-(Q3-B)") (class "Default")
      (node (ref "Q3") (pin "2") (pinfunction "B_2") (pintype "passive"))
      (node (ref "R10") (pin "2") (pinfunction "2_2") (pintype "passive"))
    )
    (net (code "31") (name "Net-(Q3-C)") (class "Default")
      (node (ref "Q3") (pin "3") (pinfunction "C_3") (pintype "passive"))
      (node (ref "R11") (pin "1") (pinfunction "1_1") (pintype "passive"))
    )
    (net (code "32") (name "Net-(Q3-E)") (class "Default")
      (node (ref "D9") (pin "C") (pinfunction "C_C") (pintype "passive"))
      (node (ref "Q3") (pin "1") (pinfunction "E_1") (pintype "passive"))
      (node (ref "R12") (pin "2") (pinfunction "2_2") (pintype "passive"))
    )
    (net (code "33") (name "Net-(Q4-B)") (class "Default")
      (node (ref "Q4") (pin "2") (pinfunction "B_2") (pintype "passive"))
      (node (ref "R14") (pin "2") (pinfunction "2_2") (pintype "passive"))
    )
    (net (code "34") (name "Net-(Q4-C)") (class "Default")
      (node (ref "Q4") (pin "3") (pinfunction "C_3") (pintype "passive"))
      (node (ref "R15") (pin "1") (pinfunction "1_1") (pintype "passive"))
    )
    (net (code "35") (name "Net-(Q4-E)") (class "Default")
      (node (ref "D12") (pin "C") (pinfunction "C_C") (pintype "passive"))
      (node (ref "Q4") (pin "1") (pinfunction "E_1") (pintype "passive"))
      (node (ref "R16") (pin "2") (pinfunction "2_2") (pintype "passive"))
    )
    (net (code "36") (name "Net-(Q5-B)") (class "Default")
      (node (ref "Q5") (pin "2") (pinfunction "B_2") (pintype "passive"))
      (node (ref "R18") (pin "2") (pinfunction "2_2") (pintype "passive"))
    )
    (net (code "37") (name "Net-(Q5-C)") (class "Default")
      (node (ref "Q5") (pin "3") (pinfunction "C_3") (pintype "passive"))
      (node (ref "R19") (pin "1") (pinfunction "1_1") (pintype "passive"))
    )
    (net (code "38") (name "Net-(Q5-E)") (class "Default")
      (node (ref "D15") (pin "C") (pinfunction "C_C") (pintype "passive"))
      (node (ref "Q5") (pin "1") (pinfunction "E_1") (pintype "passive"))
      (node (ref "R20") (pin "2") (pinfunction "2_2") (pintype "passive"))
    )
    (net (code "39") (name "Net-(Q6-B)") (class "Default")
      (node (ref "Q6") (pin "2") (pinfunction "B_2") (pintype "passive"))
      (node (ref "R22") (pin "2") (pinfunction "2_2") (pintype "passive"))
    )
    (net (code "40") (name "Net-(Q6-C)") (class "Default")
      (node (ref "Q6") (pin "3") (pinfunction "C_3") (pintype "passive"))
      (node (ref "R23") (pin "1") (pinfunction "1_1") (pintype "passive"))
    )
    (net (code "41") (name "Net-(Q6-E)") (class "Default")
      (node (ref "D18") (pin "C") (pinfunction "C_C") (pintype "passive"))
      (node (ref "Q6") (pin "1") (pinfunction "E_1") (pintype "passive"))
      (node (ref "R24") (pin "2") (pinfunction "2_2") (pintype "passive"))
    )
    (net (code "42") (name "Net-(Q7-B)") (class "Default")
      (node (ref "Q7") (pin "2") (pinfunction "B_2") (pintype "passive"))
      (node (ref "R26") (pin "2") (pinfunction "2_2") (pintype "passive"))
    )
    (net (code "43") (name "Net-(Q7-C)") (class "Default")
      (node (ref "Q7") (pin "3") (pinfunction "C_3") (pintype "passive"))
      (node (ref "R27") (pin "1") (pinfunction "1_1") (pintype "passive"))
    )
    (net (code "44") (name "Net-(Q7-E)") (class "Default")
      (node (ref "D21") (pin "C") (pinfunction "C_C") (pintype "passive"))
      (node (ref "Q7") (pin "1") (pinfunction "E_1") (pintype "passive"))
      (node (ref "R28") (pin "2") (pinfunction "2_2") (pintype "passive"))
    )
    (net (code "45") (name "Net-(Q8-B)") (class "Default")
      (node (ref "Q8") (pin "2") (pinfunction "B_2") (pintype "passive"))
      (node (ref "R30") (pin "2") (pinfunction "2_2") (pintype "passive"))
    )
    (net (code "46") (name "Net-(Q8-C)") (class "Default")
      (node (ref "Q8") (pin "3") (pinfunction "C_3") (pintype "passive"))
      (node (ref "R31") (pin "1") (pinfunction "1_1") (pintype "passive"))
    )
    (net (code "47") (name "Net-(Q8-E)") (class "Default")
      (node (ref "D24") (pin "C") (pinfunction "C_C") (pintype "passive"))
      (node (ref "Q8") (pin "1") (pinfunction "E_1") (pintype "passive"))
      (node (ref "R32") (pin "2") (pinfunction "2_2") (pintype "passive"))
    )
    (net (code "48") (name "Net-(Q9-B)") (class "Default")
      (node (ref "Q9") (pin "2") (pinfunction "B_2") (pintype "passive"))
      (node (ref "R34") (pin "2") (pinfunction "2_2") (pintype "passive"))
    )
    (net (code "49") (name "Net-(Q9-C)") (class "Default")
      (node (ref "Q9") (pin "3") (pinfunction "C_3") (pintype "passive"))
      (node (ref "R35") (pin "1") (pinfunction "1_1") (pintype "passive"))
    )
    (net (code "50") (name "Net-(Q9-E)") (class "Default")
      (node (ref "D27") (pin "C") (pinfunction "C_C") (pintype "passive"))
      (node (ref "Q9") (pin "1") (pinfunction "E_1") (pintype "passive"))
      (node (ref "R36") (pin "2") (pinfunction "2_2") (pintype "passive"))
    )
    (net (code "51") (name "Net-(Q10-B)") (class "Default")
      (node (ref "Q10") (pin "2") (pinfunction "B_2") (pintype "passive"))
      (node (ref "R38") (pin "2") (pinfunction "2_2") (pintype "passive"))
    )
    (net (code "52") (name "Net-(Q10-C)") (class "Default")
      (node (ref "Q10") (pin "3") (pinfunction "C_3") (pintype "passive"))
      (node (ref "R39") (pin "1") (pinfunction "1_1") (pintype "passive"))
    )
    (net (code "53") (name "Net-(Q10-E)") (class "Default")
      (node (ref "D30") (pin "C") (pinfunction "C_C") (pintype "passive"))
      (node (ref "Q10") (pin "1") (pinfunction "E_1") (pintype "passive"))
      (node (ref "R40") (pin "2") (pinfunction "2_2") (pintype "passive"))
    )
    (net (code "54") (name "Net-(Q11-B)") (class "Default")
      (node (ref "Q11") (pin "2") (pinfunction "B_2") (pintype "passive"))
      (node (ref "R42") (pin "2") (pinfunction "2_2") (pintype "passive"))
    )
    (net (code "55") (name "Net-(Q11-C)") (class "Default")
      (node (ref "Q11") (pin "3") (pinfunction "C_3") (pintype "passive"))
      (node (ref "R43") (pin "1") (pinfunction "1_1") (pintype "passive"))
    )
    (net (code "56") (name "Net-(Q11-E)") (class "Default")
      (node (ref "D33") (pin "C") (pinfunction "C_C") (pintype "passive"))
      (node (ref "Q11") (pin "1") (pinfunction "E_1") (pintype "passive"))
      (node (ref "R44") (pin "2") (pinfunction "2_2") (pintype "passive"))
    )
    (net (code "57") (name "Net-(Q12-B)") (class "Default")
      (node (ref "Q12") (pin "2") (pinfunction "B_2") (pintype "passive"))
      (node (ref "R46") (pin "2") (pinfunction "2_2") (pintype "passive"))
    )
    (net (code "58") (name "Net-(Q12-C)") (class "Default")
      (node (ref "Q12") (pin "3") (pinfunction "C_3") (pintype "passive"))
      (node (ref "R47") (pin "1") (pinfunction "1_1") (pintype "passive"))
    )
    (net (code "59") (name "Net-(Q12-E)") (class "Default")
      (node (ref "D36") (pin "C") (pinfunction "C_C") (pintype "passive"))
      (node (ref "Q12") (pin "1") (pinfunction "E_1") (pintype "passive"))
      (node (ref "R48") (pin "2") (pinfunction "2_2") (pintype "passive"))
    )
    (net (code "60") (name "Net-(Q13-B)") (class "Default")
      (node (ref "Q13") (pin "2") (pinfunction "B_2") (pintype "passive"))
      (node (ref "R50") (pin "2") (pinfunction "2_2") (pintype "passive"))
    )
    (net (code "61") (name "Net-(Q13-C)") (class "Default")
      (node (ref "Q13") (pin "3") (pinfunction "C_3") (pintype "passive"))
      (node (ref "R51") (pin "1") (pinfunction "1_1") (pintype "passive"))
    )
    (net (code "62") (name "Net-(Q13-E)") (class "Default")
      (node (ref "D39") (pin "C") (pinfunction "C_C") (pintype "passive"))
      (node (ref "Q13") (pin "1") (pinfunction "E_1") (pintype "passive"))
      (node (ref "R52") (pin "2") (pinfunction "2_2") (pintype "passive"))
    )
    (net (code "63") (name "Net-(Q14-B)") (class "Default")
      (node (ref "Q14") (pin "2") (pinfunction "B_2") (pintype "passive"))
      (node (ref "R54") (pin "2") (pinfunction "2_2") (pintype "passive"))
    )
    (net (code "64") (name "Net-(Q14-C)") (class "Default")
      (node (ref "Q14") (pin "3") (pinfunction "C_3") (pintype "passive"))
      (node (ref "R55") (pin "1") (pinfunction "1_1") (pintype "passive"))
    )
    (net (code "65") (name "Net-(Q14-E)") (class "Default")
      (node (ref "D42") (pin "C") (pinfunction "C_C") (pintype "passive"))
      (node (ref "Q14") (pin "1") (pinfunction "E_1") (pintype "passive"))
      (node (ref "R56") (pin "2") (pinfunction "2_2") (pintype "passive"))
    )
    (net (code "66") (name "Net-(Q15-B)") (class "Default")
      (node (ref "Q15") (pin "2") (pinfunction "B_2") (pintype "passive"))
      (node (ref "R58") (pin "2") (pinfunction "2_2") (pintype "passive"))
    )
    (net (code "67") (name "Net-(Q15-C)") (class "Default")
      (node (ref "Q15") (pin "3") (pinfunction "C_3") (pintype "passive"))
      (node (ref "R59") (pin "1") (pinfunction "1_1") (pintype "passive"))
    )
    (net (code "68") (name "Net-(Q15-E)") (class "Default")
      (node (ref "D45") (pin "C") (pinfunction "C_C") (pintype "passive"))
      (node (ref "Q15") (pin "1") (pinfunction "E_1") (pintype "passive"))
      (node (ref "R60") (pin "2") (pinfunction "2_2") (pintype "passive"))
    )
    (net (code "69") (name "Net-(Q16-B)") (class "Default")
      (node (ref "Q16") (pin "2") (pinfunction "B_2") (pintype "passive"))
      (node (ref "R62") (pin "2") (pinfunction "2_2") (pintype "passive"))
    )
    (net (code "70") (name "Net-(Q16-C)") (class "Default")
      (node (ref "Q16") (pin "3") (pinfunction "C_3") (pintype "passive"))
      (node (ref "R63") (pin "1") (pinfunction "1_1") (pintype "passive"))
    )
    (net (code "71") (name "Net-(Q16-E)") (class "Default")
      (node (ref "D48") (pin "C") (pinfunction "C_C") (pintype "passive"))
      (node (ref "Q16") (pin "1") (pinfunction "E_1") (pintype "passive"))
      (node (ref "R64") (pin "2") (pinfunction "2_2") (pintype "passive"))
    )
    (net (code "72") (name "Net-(Q17-B)") (class "Default")
      (node (ref "Q17") (pin "2") (pinfunction "B_2") (pintype "passive"))
      (node (ref "R66") (pin "2") (pinfunction "2_2") (pintype "passive"))
    )
    (net (code "73") (name "Net-(Q17-C)") (class "Default")
      (node (ref "Q17") (pin "3") (pinfunction "C_3") (pintype "passive"))
      (node (ref "R67") (pin "1") (pinfunction "1_1") (pintype "passive"))
    )
    (net (code "74") (name "Net-(Q17-E)") (class "Default")
      (node (ref "D51") (pin "C") (pinfunction "C_C") (pintype "passive"))
      (node (ref "Q17") (pin "1") (pinfunction "E_1") (pintype "passive"))
      (node (ref "R68") (pin "2") (pinfunction "2_2") (pintype "passive"))
    )
    (net (code "75") (name "Net-(Q18-B)") (class "Default")
      (node (ref "Q18") (pin "2") (pinfunction "B_2") (pintype "passive"))
      (node (ref "R70") (pin "2") (pinfunction "2_2") (pintype "passive"))
    )
    (net (code "76") (name "Net-(Q18-C)") (class "Default")
      (node (ref "Q18") (pin "3") (pinfunction "C_3") (pintype "passive"))
      (node (ref "R71") (pin "1") (pinfunction "1_1") (pintype "passive"))
    )
    (net (code "77") (name "Net-(Q18-E)") (class "Default")
      (node (ref "D54") (pin "C") (pinfunction "C_C") (pintype "passive"))
      (node (ref "Q18") (pin "1") (pinfunction "E_1") (pintype "passive"))
      (node (ref "R72") (pin "2") (pinfunction "2_2") (pintype "passive"))
    )
    (net (code "78") (name "VCC") (class "Default")
      (node (ref "R11") (pin "2") (pinfunction "2_2") (pintype "passive"))
      (node (ref "R15") (pin "2") (pinfunction "2_2") (pintype "passive"))
      (node (ref "R19") (pin "2") (pinfunction "2_2") (pintype "passive"))
      (node (ref "R23") (pin "2") (pinfunction "2_2") (pintype "passive"))
      (node (ref "R27") (pin "2") (pinfunction "2_2") (pintype "passive"))
      (node (ref "R3") (pin "2") (pinfunction "2_2") (pintype "passive"))
      (node (ref "R31") (pin "2") (pinfunction "2_2") (pintype "passive"))
      (node (ref "R35") (pin "2") (pinfunction "2_2") (pintype "passive"))
      (node (ref "R39") (pin "2") (pinfunction "2_2") (pintype "passive"))
      (node (ref "R43") (pin "2") (pinfunction "2_2") (pintype "passive"))
      (node (ref "R47") (pin "2") (pinfunction "2_2") (pintype "passive"))
      (node (ref "R51") (pin "2") (pinfunction "2_2") (pintype "passive"))
      (node (ref "R55") (pin "2") (pinfunction "2_2") (pintype "passive"))
      (node (ref "R59") (pin "2") (pinfunction "2_2") (pintype "passive"))
      (node (ref "R63") (pin "2") (pinfunction "2_2") (pintype "passive"))
      (node (ref "R67") (pin "2") (pinfunction "2_2") (pintype "passive"))
      (node (ref "R7") (pin "2") (pinfunction "2_2") (pintype "passive"))
      (node (ref "R71") (pin "2") (pinfunction "2_2") (pintype "passive"))
      (node (ref "U$1") (pin "A2") (pinfunction "1_A2") (pintype "bidirectional"))
    )
    (net (code "79") (name "unconnected-(E1A-A1-Pad2)") (class "Default")
      (node (ref "E1") (pin "2") (pinfunction "A1_2") (pintype "input"))
    )
    (net (code "80") (name "unconnected-(E1A-A2-Pad4)") (class "Default")
      (node (ref "E1") (pin "4") (pinfunction "A2_4") (pintype "input"))
    )
    (net (code "81") (name "unconnected-(E1A-A3-Pad6)") (class "Default")
      (node (ref "E1") (pin "6") (pinfunction "A3_6") (pintype "input"))
    )
    (net (code "82") (name "unconnected-(E1A-Y1-Pad18)") (class "Default")
      (node (ref "E1") (pin "18") (pinfunction "Y1_18") (pintype "tri_state"))
    )
    (net (code "83") (name "unconnected-(E1A-Y2-Pad16)") (class "Default")
      (node (ref "E1") (pin "16") (pinfunction "Y2_16") (pintype "tri_state"))
    )
    (net (code "84") (name "unconnected-(E1A-Y3-Pad14)") (class "Default")
      (node (ref "E1") (pin "14") (pinfunction "Y3_14") (pintype "tri_state"))
    )
    (net (code "85") (name "unconnected-(E1A-Y4-Pad12)") (class "Default")
      (node (ref "E1") (pin "12") (pinfunction "Y4_12") (pintype "tri_state"))
    )
    (net (code "86") (name "unconnected-(E1B-A1-Pad11)") (class "Default")
      (node (ref "E1") (pin "11") (pinfunction "A1_11") (pintype "input"))
    )
    (net (code "87") (name "unconnected-(E1B-A2-Pad13)") (class "Default")
      (node (ref "E1") (pin "13") (pinfunction "A2_13") (pintype "input"))
    )
    (net (code "88") (name "unconnected-(E1B-A3-Pad15)") (class "Default")
      (node (ref "E1") (pin "15") (pinfunction "A3_15") (pintype "input"))
    )
    (net (code "89") (name "unconnected-(E1B-Y1-Pad9)") (class "Default")
      (node (ref "E1") (pin "9") (pinfunction "Y1_9") (pintype "tri_state"))
    )
    (net (code "90") (name "unconnected-(E1B-Y2-Pad7)") (class "Default")
      (node (ref "E1") (pin "7") (pinfunction "Y2_7") (pintype "tri_state"))
    )
    (net (code "91") (name "unconnected-(E1B-Y3-Pad5)") (class "Default")
      (node (ref "E1") (pin "5") (pinfunction "Y3_5") (pintype "tri_state"))
    )
    (net (code "92") (name "unconnected-(E1B-Y4-Pad3)") (class "Default")
      (node (ref "E1") (pin "3") (pinfunction "Y4_3") (pintype "tri_state"))
    )
    (net (code "93") (name "unconnected-(E2A-A1-Pad2)") (class "Default")
      (node (ref "E2") (pin "2") (pinfunction "A1_2") (pintype "input"))
    )
    (net (code "94") (name "unconnected-(E2A-A2-Pad4)") (class "Default")
      (node (ref "E2") (pin "4") (pinfunction "A2_4") (pintype "input"))
    )
    (net (code "95") (name "unconnected-(E2A-A3-Pad6)") (class "Default")
      (node (ref "E2") (pin "6") (pinfunction "A3_6") (pintype "input"))
    )
    (net (code "96") (name "unconnected-(E2A-Y1-Pad18)") (class "Default")
      (node (ref "E2") (pin "18") (pinfunction "Y1_18") (pintype "tri_state"))
    )
    (net (code "97") (name "unconnected-(E2A-Y2-Pad16)") (class "Default")
      (node (ref "E2") (pin "16") (pinfunction "Y2_16") (pintype "tri_state"))
    )
    (net (code "98") (name "unconnected-(E2A-Y3-Pad14)") (class "Default")
      (node (ref "E2") (pin "14") (pinfunction "Y3_14") (pintype "tri_state"))
    )
    (net (code "99") (name "unconnected-(E2A-Y4-Pad12)") (class "Default")
      (node (ref "E2") (pin "12") (pinfunction "Y4_12") (pintype "tri_state"))
    )
    (net (code "100") (name "unconnected-(E2B-A1-Pad11)") (class "Default")
      (node (ref "E2") (pin "11") (pinfunction "A1_11") (pintype "input"))
    )
    (net (code "101") (name "unconnected-(E2B-A2-Pad13)") (class "Default")
      (node (ref "E2") (pin "13") (pinfunction "A2_13") (pintype "input"))
    )
    (net (code "102") (name "unconnected-(E2B-A3-Pad15)") (class "Default")
      (node (ref "E2") (pin "15") (pinfunction "A3_15") (pintype "input"))
    )
    (net (code "103") (name "unconnected-(E2B-Y1-Pad9)") (class "Default")
      (node (ref "E2") (pin "9") (pinfunction "Y1_9") (pintype "tri_state"))
    )
    (net (code "104") (name "unconnected-(E2B-Y2-Pad7)") (class "Default")
      (node (ref "E2") (pin "7") (pinfunction "Y2_7") (pintype "tri_state"))
    )
    (net (code "105") (name "unconnected-(E2B-Y3-Pad5)") (class "Default")
      (node (ref "E2") (pin "5") (pinfunction "Y3_5") (pintype "tri_state"))
    )
    (net (code "106") (name "unconnected-(E2B-Y4-Pad3)") (class "Default")
      (node (ref "E2") (pin "3") (pinfunction "Y4_3") (pintype "tri_state"))
    )
    (net (code "107") (name "unconnected-(E3A-A1-Pad2)") (class "Default")
      (node (ref "E3") (pin "2") (pinfunction "A1_2") (pintype "input"))
    )
    (net (code "108") (name "unconnected-(E3A-A2-Pad4)") (class "Default")
      (node (ref "E3") (pin "4") (pinfunction "A2_4") (pintype "input"))
    )
    (net (code "109") (name "unconnected-(E3A-A3-Pad6)") (class "Default")
      (node (ref "E3") (pin "6") (pinfunction "A3_6") (pintype "input"))
    )
    (net (code "110") (name "unconnected-(E3A-Y1-Pad18)") (class "Default")
      (node (ref "E3") (pin "18") (pinfunction "Y1_18") (pintype "tri_state"))
    )
    (net (code "111") (name "unconnected-(E3A-Y2-Pad16)") (class "Default")
      (node (ref "E3") (pin "16") (pinfunction "Y2_16") (pintype "tri_state"))
    )
    (net (code "112") (name "unconnected-(E3A-Y3-Pad14)") (class "Default")
      (node (ref "E3") (pin "14") (pinfunction "Y3_14") (pintype "tri_state"))
    )
    (net (code "113") (name "unconnected-(E3A-Y4-Pad12)") (class "Default")
      (node (ref "E3") (pin "12") (pinfunction "Y4_12") (pintype "tri_state"))
    )
    (net (code "114") (name "unconnected-(E3B-A1-Pad11)") (class "Default")
      (node (ref "E3") (pin "11") (pinfunction "A1_11") (pintype "input"))
    )
    (net (code "115") (name "unconnected-(E3B-A2-Pad13)") (class "Default")
      (node (ref "E3") (pin "13") (pinfunction "A2_13") (pintype "input"))
    )
    (net (code "116") (name "unconnected-(E3B-A3-Pad15)") (class "Default")
      (node (ref "E3") (pin "15") (pinfunction "A3_15") (pintype "input"))
    )
    (net (code "117") (name "unconnected-(E3B-Y1-Pad9)") (class "Default")
      (node (ref "E3") (pin "9") (pinfunction "Y1_9") (pintype "tri_state"))
    )
    (net (code "118") (name "unconnected-(E3B-Y2-Pad7)") (class "Default")
      (node (ref "E3") (pin "7") (pinfunction "Y2_7") (pintype "tri_state"))
    )
    (net (code "119") (name "unconnected-(E3B-Y3-Pad5)") (class "Default")
      (node (ref "E3") (pin "5") (pinfunction "Y3_5") (pintype "tri_state"))
    )
    (net (code "120") (name "unconnected-(E3B-Y4-Pad3)") (class "Default")
      (node (ref "E3") (pin "3") (pinfunction "Y4_3") (pintype "tri_state"))
    )
    (net (code "121") (name "unconnected-(U$1AC-1-PadS1)") (class "Default")
      (node (ref "U$1") (pin "S1") (pinfunction "1_S1") (pintype "bidirectional"))
    )
    (net (code "122") (name "unconnected-(U$1AD-1-PadS2)") (class "Default")
      (node (ref "U$1") (pin "S2") (pinfunction "1_S2") (pintype "bidirectional"))
    )
    (net (code "123") (name "unconnected-(U$1AF-1-PadT2)") (class "Default")
      (node (ref "U$1") (pin "T2") (pinfunction "1_T2") (pintype "bidirectional"))
    )
    (net (code "124") (name "unconnected-(U$1AJ-1-PadV2)") (class "Default")
      (node (ref "U$1") (pin "V2") (pinfunction "1_V2") (pintype "bidirectional"))
    )
    (net (code "125") (name "unconnected-(U$1C-1-PadB1)") (class "Default")
      (node (ref "U$1") (pin "B1") (pinfunction "1_B1") (pintype "bidirectional"))
    )
    (net (code "126") (name "unconnected-(U$1G-1-PadD1)") (class "Default")
      (node (ref "U$1") (pin "D1") (pinfunction "1_D1") (pintype "bidirectional"))
    )
    (net (code "127") (name "unconnected-(U$1H-1-PadD2)") (class "Default")
      (node (ref "U$1") (pin "D2") (pinfunction "1_D2") (pintype "bidirectional"))
    )
    (net (code "128") (name "unconnected-(U$1I-1-PadE1)") (class "Default")
      (node (ref "U$1") (pin "E1") (pinfunction "1_E1") (pintype "bidirectional"))
    )
    (net (code "129") (name "unconnected-(U$1J-1-PadE2)") (class "Default")
      (node (ref "U$1") (pin "E2") (pinfunction "1_E2") (pintype "bidirectional"))
    )
    (net (code "130") (name "unconnected-(U$1M-1-PadH1)") (class "Default")
      (node (ref "U$1") (pin "H1") (pinfunction "1_H1") (pintype "bidirectional"))
    )
    (net (code "131") (name "unconnected-(U$1N-1-PadH2)") (class "Default")
      (node (ref "U$1") (pin "H2") (pinfunction "1_H2") (pintype "bidirectional"))
    )
    (net (code "132") (name "unconnected-(U$1O-1-PadJ1)") (class "Default")
      (node (ref "U$1") (pin "J1") (pinfunction "1_J1") (pintype "bidirectional"))
    )
    (net (code "133") (name "unconnected-(U$1R-1-PadK2)") (class "Default")
      (node (ref "U$1") (pin "K2") (pinfunction "1_K2") (pintype "bidirectional"))
    )
    (net (code "134") (name "unconnected-(U$1S-1-PadL1)") (class "Default")
      (node (ref "U$1") (pin "L1") (pinfunction "1_L1") (pintype "bidirectional"))
    )
    (net (code "135") (name "unconnected-(U$1U-1-PadM1)") (class "Default")
      (node (ref "U$1") (pin "M1") (pinfunction "1_M1") (pintype "bidirectional"))
    )
    (net (code "136") (name "unconnected-(U$1V-1-PadM2)") (class "Default")
      (node (ref "U$1") (pin "M2") (pinfunction "1_M2") (pintype "bidirectional"))
    )
    (net (code "137") (name "unconnected-(U$1Y-1-PadP1)") (class "Default")
      (node (ref "U$1") (pin "P1") (pinfunction "1_P1") (pintype "bidirectional"))
    )
    (net (code "138") (name "unconnected-(U$1Z-1-PadP2)") (class "Default")
      (node (ref "U$1") (pin "P2") (pinfunction "1_P2") (pintype "bidirectional"))
    )
  )
)
